# Power.net
KiCad netlist of a schematic drawn in Altium Designer
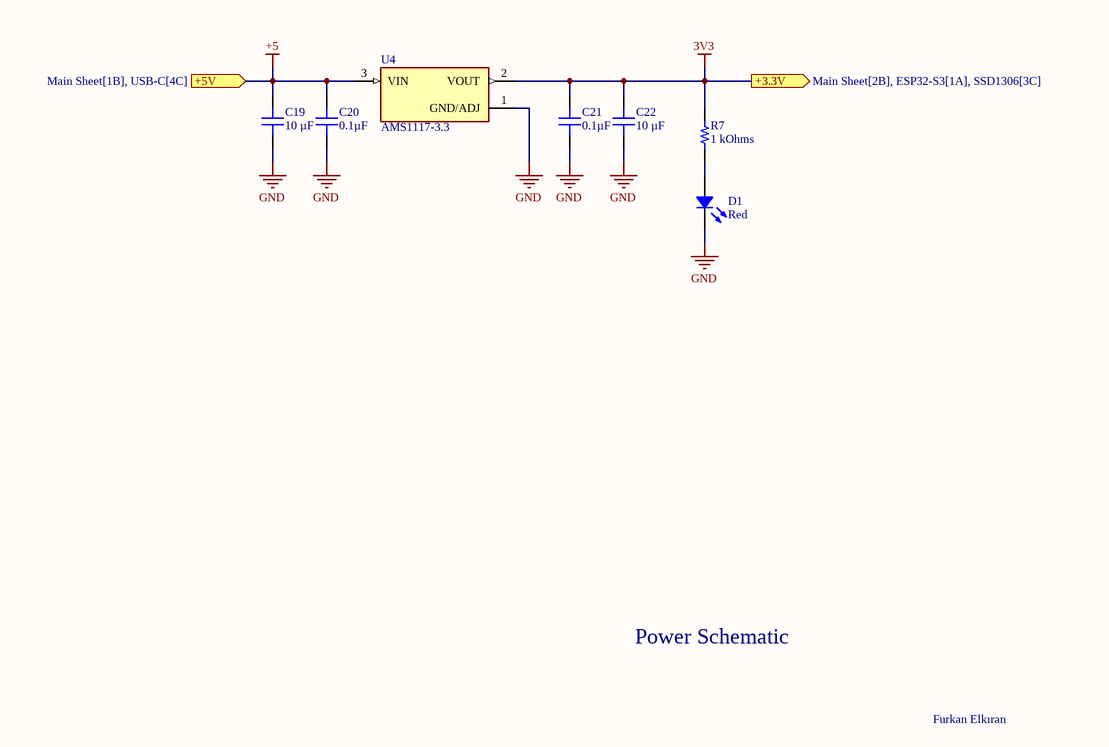
[diagram p0: Power.SchDoc]

(export (version "E")
  (design (tool "Eeschema 10.0.6"))
  (components
    (comp (ref "C19")
      (value "10 µF")
      (footprint "CAP 0805_2012")
      (description "CAP CER 10UF 25V X6S 0805")
      (fields
        (field (name "PART NUMBER") "CL21X106KAYNNNE")
        (field (name "CAPACITANCE") "10 µF")
        (field (name "MANUFACTURER") "Samsung Electro-Mechanics")
      )
      (libsource (lib "Celestial Altium Library - altium_library") (part "Capacitor"))
    )
    (comp (ref "C20")
      (value "0.1µF")
      (footprint "CAP 0805_2012")
      (description "CAP CER 0.1UF 50V X7R 0805")
      (fields
        (field (name "PART NUMBER") "LD055C104KAB2A")
        (field (name "CAPACITANCE") "0.1µF")
        (field (name "MANUFACTURER") "AVX Corporation")
      )
      (libsource (lib "Celestial Altium Library - altium_library") (part "Capacitor"))
    )
    (comp (ref "C21")
      (value "0.1µF")
      (footprint "CAP 0805_2012")
      (description "CAP CER 0.1UF 50V X7R 0805")
      (fields
        (field (name "PART NUMBER") "LD055C104KAB2A")
        (field (name "CAPACITANCE") "0.1µF")
        (field (name "MANUFACTURER") "AVX Corporation")
      )
      (libsource (lib "Celestial Altium Library - altium_library") (part "Capacitor"))
    )
    (comp (ref "C22")
      (value "10 µF")
      (footprint "CAP 0805_2012")
      (description "CAP CER 10UF 25V X6S 0805")
      (fields
        (field (name "PART NUMBER") "CL21X106KAYNNNE")
        (field (name "CAPACITANCE") "10 µF")
        (field (name "MANUFACTURER") "Samsung Electro-Mechanics")
      )
      (libsource (lib "Celestial Altium Library - altium_library") (part "Capacitor"))
    )
    (comp (ref "D1")
      (value "Red")
      (footprint "LED 0603_1608 RED")
      (description "0603 LED RED 623NM DOMINANT, 628")
      (fields (field (name "PART NUMBER") "QBLP601-R1") (field (name "MANUFACTURER") "QT Brightek (QTB)"))
      (libsource (lib "Celestial Altium Library - altium_library") (part "LED"))
    )
    (comp (ref "R7")
      (value "1 kOhms")
      (footprint "RES 0402_1005")
      (description "RES SMD 1K OHM 5% 1/5W 0402")
      (fields (field (name "PART NUMBER") "CRCW04021K00JNEDHP") (field (name "MANUFACTURER") "Vishay Dale"))
      (libsource (lib "Celestial Altium Library - altium_library") (part "Resistor"))
    )
    (comp (ref "U4")
      (value "AMS1117-3.3")
      (footprint "SOT229P700X180-4N")
      (description "Sot223/Pkg 1-Amp 3.3-Volt Low Drop Out Voltage Regulatator")
      (fields (field (name "MF") "Advanced Monolithic Systems"))
      (libsource (lib "AMS1117-3.3") (part "AMS1117-3.3"))
    )
  )
  (nets
    (net (code "1") (name "+5") (class "Default")
      (node (ref "C19") (pin "2") (pinfunction "2_2") (pintype "passive"))
      (node (ref "C20") (pin "2") (pinfunction "2_2") (pintype "passive"))
      (node (ref "U4") (pin "3") (pinfunction "VIN_3") (pintype "input"))
    )
    (net (code "2") (name "3V3") (class "Default")
      (node (ref "C21") (pin "2") (pinfunction "2_2") (pintype "passive"))
      (node (ref "C22") (pin "2") (pinfunction "2_2") (pintype "passive"))
      (node (ref "R7") (pin "2") (pinfunction "2_2") (pintype "passive"))
      (node (ref "U4") (pin "2") (pinfunction "VOUT_2") (pintype "output"))
    )
    (net (code "3") (name "GND") (class "Default")
      (node (ref "C19") (pin "1") (pinfunction "1_1") (pintype "passive"))
      (node (ref "C20") (pin "1") (pinfunction "1_1") (pintype "passive"))
      (node (ref "C21") (pin "1") (pinfunction "1_1") (pintype "passive"))
      (node (ref "C22") (pin "1") (pinfunction "1_1") (pintype "passive"))
      (node (ref "D1") (pin "2") (pinfunction "2_2") (pintype "passive"))
      (node (ref "U4") (pin "1") (pinfunction "GND/ADJ_1") (pintype "power_in"))
    )
    (net (code "4") (name "Net-(D1-Pad1)") (class "Default")
      (node (ref "D1") (pin "1") (pinfunction "1_1") (pintype "passive"))
      (node (ref "R7") (pin "1") (pinfunction "1_1") (pintype "passive"))
    )
  )
)
